# servo_7seg.net
KiCad netlist of a schematic drawn in EAGLE
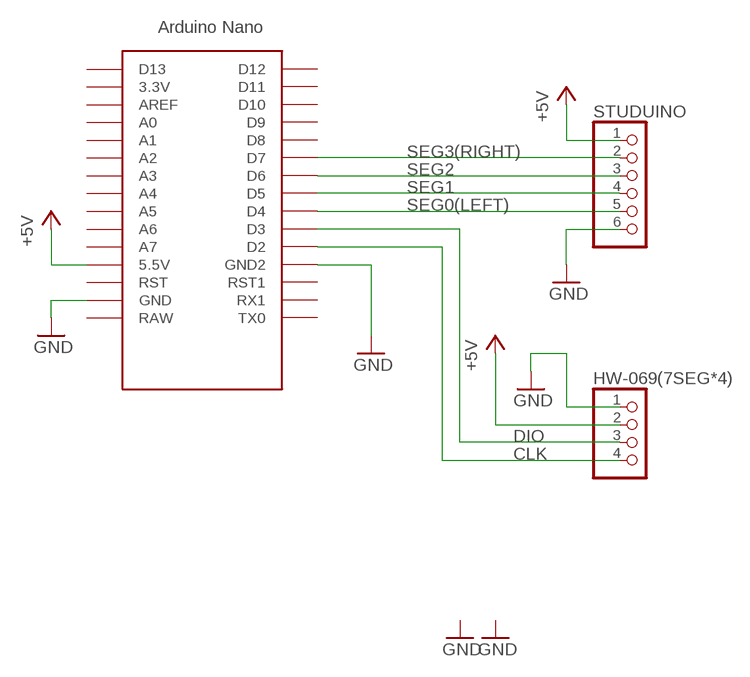
[diagram p0: schematic, sheet 1]

(export (version "E")
  (design (tool "Eeschema 10.0.6"))
  (components
    (comp (ref "HW-069(7SEG*4)")
      (value "PINHD-1X4")
      (footprint "eagle-import:1X04")
      (libsource (lib "eagle-import") (part "PINHD-1X4"))
    )
    (comp (ref "STUDUINO")
      (value "PINHD-1X6")
      (footprint "eagle-import:1X06")
      (libsource (lib "eagle-import") (part "PINHD-1X6"))
    )
    (comp (ref "U$1")
      (value "NANO")
      (footprint "eagle-import:NANO")
      (libsource (lib "eagle-import") (part "NANO"))
    )
  )
  (nets
    (net (code "1") (name "+5V") (class "Default")
      (node (ref "HW-069(7SEG*4)") (pin "2") (pinfunction "2_2") (pintype "passive"))
      (node (ref "STUDUINO") (pin "1") (pinfunction "1_1") (pintype "passive"))
      (node (ref "U$1") (pin "5V") (pinfunction "5.5V_5V") (pintype "bidirectional"))
    )
    (net (code "2") (name "/CLK") (class "Default")
      (node (ref "HW-069(7SEG*4)") (pin "4") (pinfunction "4_4") (pintype "passive"))
      (node (ref "U$1") (pin "D2") (pinfunction "D2_D2") (pintype "bidirectional"))
    )
    (net (code "3") (name "/DIO") (class "Default")
      (node (ref "HW-069(7SEG*4)") (pin "3") (pinfunction "3_3") (pintype "passive"))
      (node (ref "U$1") (pin "D3") (pinfunction "D3_D3") (pintype "bidirectional"))
    )
    (net (code "4") (name "/SEG0(LEFT)") (class "Default")
      (node (ref "STUDUINO") (pin "5") (pinfunction "5_5") (pintype "passive"))
      (node (ref "U$1") (pin "D4") (pinfunction "D4_D4") (pintype "bidirectional"))
    )
    (net (code "5") (name "/SEG1") (class "Default")
      (node (ref "STUDUINO") (pin "4") (pinfunction "4_4") (pintype "passive"))
      (node (ref "U$1") (pin "D5") (pinfunction "D5_D5") (pintype "bidirectional"))
    )
    (net (code "6") (name "/SEG2") (class "Default")
      (node (ref "STUDUINO") (pin "3") (pinfunction "3_3") (pintype "passive"))
      (node (ref "U$1") (pin "D6") (pinfunction "D6_D6") (pintype "bidirectional"))
    )
    (net (code "7") (name "/SEG3(RIGHT)") (class "Default")
      (node (ref "STUDUINO") (pin "2") (pinfunction "2_2") (pintype "passive"))
      (node (ref "U$1") (pin "D7") (pinfunction "D7_D7") (pintype "bidirectional"))
    )
    (net (code "8") (name "GND") (class "Default")
      (node (ref "HW-069(7SEG*4)") (pin "1") (pinfunction "1_1") (pintype "passive"))
      (node (ref "STUDUINO") (pin "6") (pinfunction "6_6") (pintype "passive"))
      (node (ref "U$1") (pin "GND") (pinfunction "GND_GND") (pintype "bidirectional"))
      (node (ref "U$1") (pin "GND1") (pinfunction "GND2_GND1") (pintype "bidirectional"))
    )
    (net (code "9") (name "unconnected-(U$1-Pad3.3V)") (class "Default")
      (node (ref "U$1") (pin "3.3V") (pinfunction "3.3V_3.3V") (pintype "bidirectional"))
    )
    (net (code "10") (name "unconnected-(U$1-PadA0)") (class "Default")
      (node (ref "U$1") (pin "A0") (pinfunction "A0_A0") (pintype "bidirectional"))
    )
    (net (code "11") (name "unconnected-(U$1-PadA1)") (class "Default")
      (node (ref "U$1") (pin "A1") (pinfunction "A1_A1") (pintype "bidirectional"))
    )
    (net (code "12") (name "unconnected-(U$1-PadA2)") (class "Default")
      (node (ref "U$1") (pin "A2") (pinfunction "A2_A2") (pintype "bidirectional"))
    )
    (net (code "13") (name "unconnected-(U$1-PadA3)") (class "Default")
      (node (ref "U$1") (pin "A3") (pinfunction "A3_A3") (pintype "bidirectional"))
    )
    (net (code "14") (name "unconnected-(U$1-PadA4)") (class "Default")
      (node (ref "U$1") (pin "A4") (pinfunction "A4_A4") (pintype "bidirectional"))
    )
    (net (code "15") (name "unconnected-(U$1-PadA5)") (class "Default")
      (node (ref "U$1") (pin "A5") (pinfunction "A5_A5") (pintype "bidirectional"))
    )
    (net (code "16") (name "unconnected-(U$1-PadA6)") (class "Default")
      (node (ref "U$1") (pin "A6") (pinfunction "A6_A6") (pintype "bidirectional"))
    )
    (net (code "17") (name "unconnected-(U$1-PadA7)") (class "Default")
      (node (ref "U$1") (pin "A7") (pinfunction "A7_A7") (pintype "bidirectional"))
    )
    (net (code "18") (name "unconnected-(U$1-PadAREF)") (class "Default")
      (node (ref "U$1") (pin "AREF") (pinfunction "AREF_AREF") (pintype "bidirectional"))
    )
    (net (code "19") (name "unconnected-(U$1-PadD8)") (class "Default")
      (node (ref "U$1") (pin "D8") (pinfunction "D8_D8") (pintype "bidirectional"))
    )
    (net (code "20") (name "unconnected-(U$1-PadD9)") (class "Default")
      (node (ref "U$1") (pin "D9") (pinfunction "D9_D9") (pintype "bidirectional"))
    )
    (net (code "21") (name "unconnected-(U$1-PadD10)") (class "Default")
      (node (ref "U$1") (pin "D10") (pinfunction "D10_D10") (pintype "bidirectional"))
    )
    (net (code "22") (name "unconnected-(U$1-PadD11)") (class "Default")
      (node (ref "U$1") (pin "D11") (pinfunction "D11_D11") (pintype "bidirectional"))
    )
    (net (code "23") (name "unconnected-(U$1-PadD12)") (class "Default")
      (node (ref "U$1") (pin "D12") (pinfunction "D12_D12") (pintype "bidirectional"))
    )
    (net (code "24") (name "unconnected-(U$1-PadD13)") (class "Default")
      (node (ref "U$1") (pin "D13") (pinfunction "D13_D13") (pintype "bidirectional"))
    )
    (net (code "25") (name "unconnected-(U$1-PadICSP1)") (class "Default")
      (node (ref "U$1") (pin "ICSP1") (pinfunction "ICSP1_ICSP1") (pintype "bidirectional"))
    )
    (net (code "26") (name "unconnected-(U$1-PadICSP2)") (class "Default")
      (node (ref "U$1") (pin "ICSP2") (pinfunction "ICSP2_ICSP2") (pintype "bidirectional"))
    )
    (net (code "27") (name "unconnected-(U$1-PadICSP3)") (class "Default")
      (node (ref "U$1") (pin "ICSP3") (pinfunction "ICSP3_ICSP3") (pintype "bidirectional"))
    )
    (net (code "28") (name "unconnected-(U$1-PadICSP4)") (class "Default")
      (node (ref "U$1") (pin "ICSP4") (pinfunction "ICSP4_ICSP4") (pintype "bidirectional"))
    )
    (net (code "29") (name "unconnected-(U$1-PadICSP5)") (class "Default")
      (node (ref "U$1") (pin "ICSP5") (pinfunction "ICSP5_ICSP5") (pintype "bidirectional"))
    )
    (net (code "30") (name "unconnected-(U$1-PadICSP6)") (class "Default")
      (node (ref "U$1") (pin "ICSP6") (pinfunction "ICSP6_ICSP6") (pintype "bidirectional"))
    )
    (net (code "31") (name "unconnected-(U$1-PadRAW)") (class "Default")
      (node (ref "U$1") (pin "RAW") (pinfunction "RAW_RAW") (pintype "bidirectional"))
    )
    (net (code "32") (name "unconnected-(U$1-PadRST)") (class "Default")
      (node (ref "U$1") (pin "RST") (pinfunction "RST_RST") (pintype "bidirectional"))
    )
    (net (code "33") (name "unconnected-(U$1-PadRST1)") (class "Default")
      (node (ref "U$1") (pin "RST1") (pinfunction "RST1_RST1") (pintype "bidirectional"))
    )
    (net (code "34") (name "unconnected-(U$1-PadRX1)") (class "Default")
      (node (ref "U$1") (pin "RX1") (pinfunction "RX1_RX1") (pintype "bidirectional"))
    )
    (net (code "35") (name "unconnected-(U$1-PadTX0)") (class "Default")
      (node (ref "U$1") (pin "TX0") (pinfunction "TX0_TX0") (pintype "bidirectional"))
    )
  )
)
